# T-11_Version_5.net
KiCad netlist of a schematic drawn in EAGLE
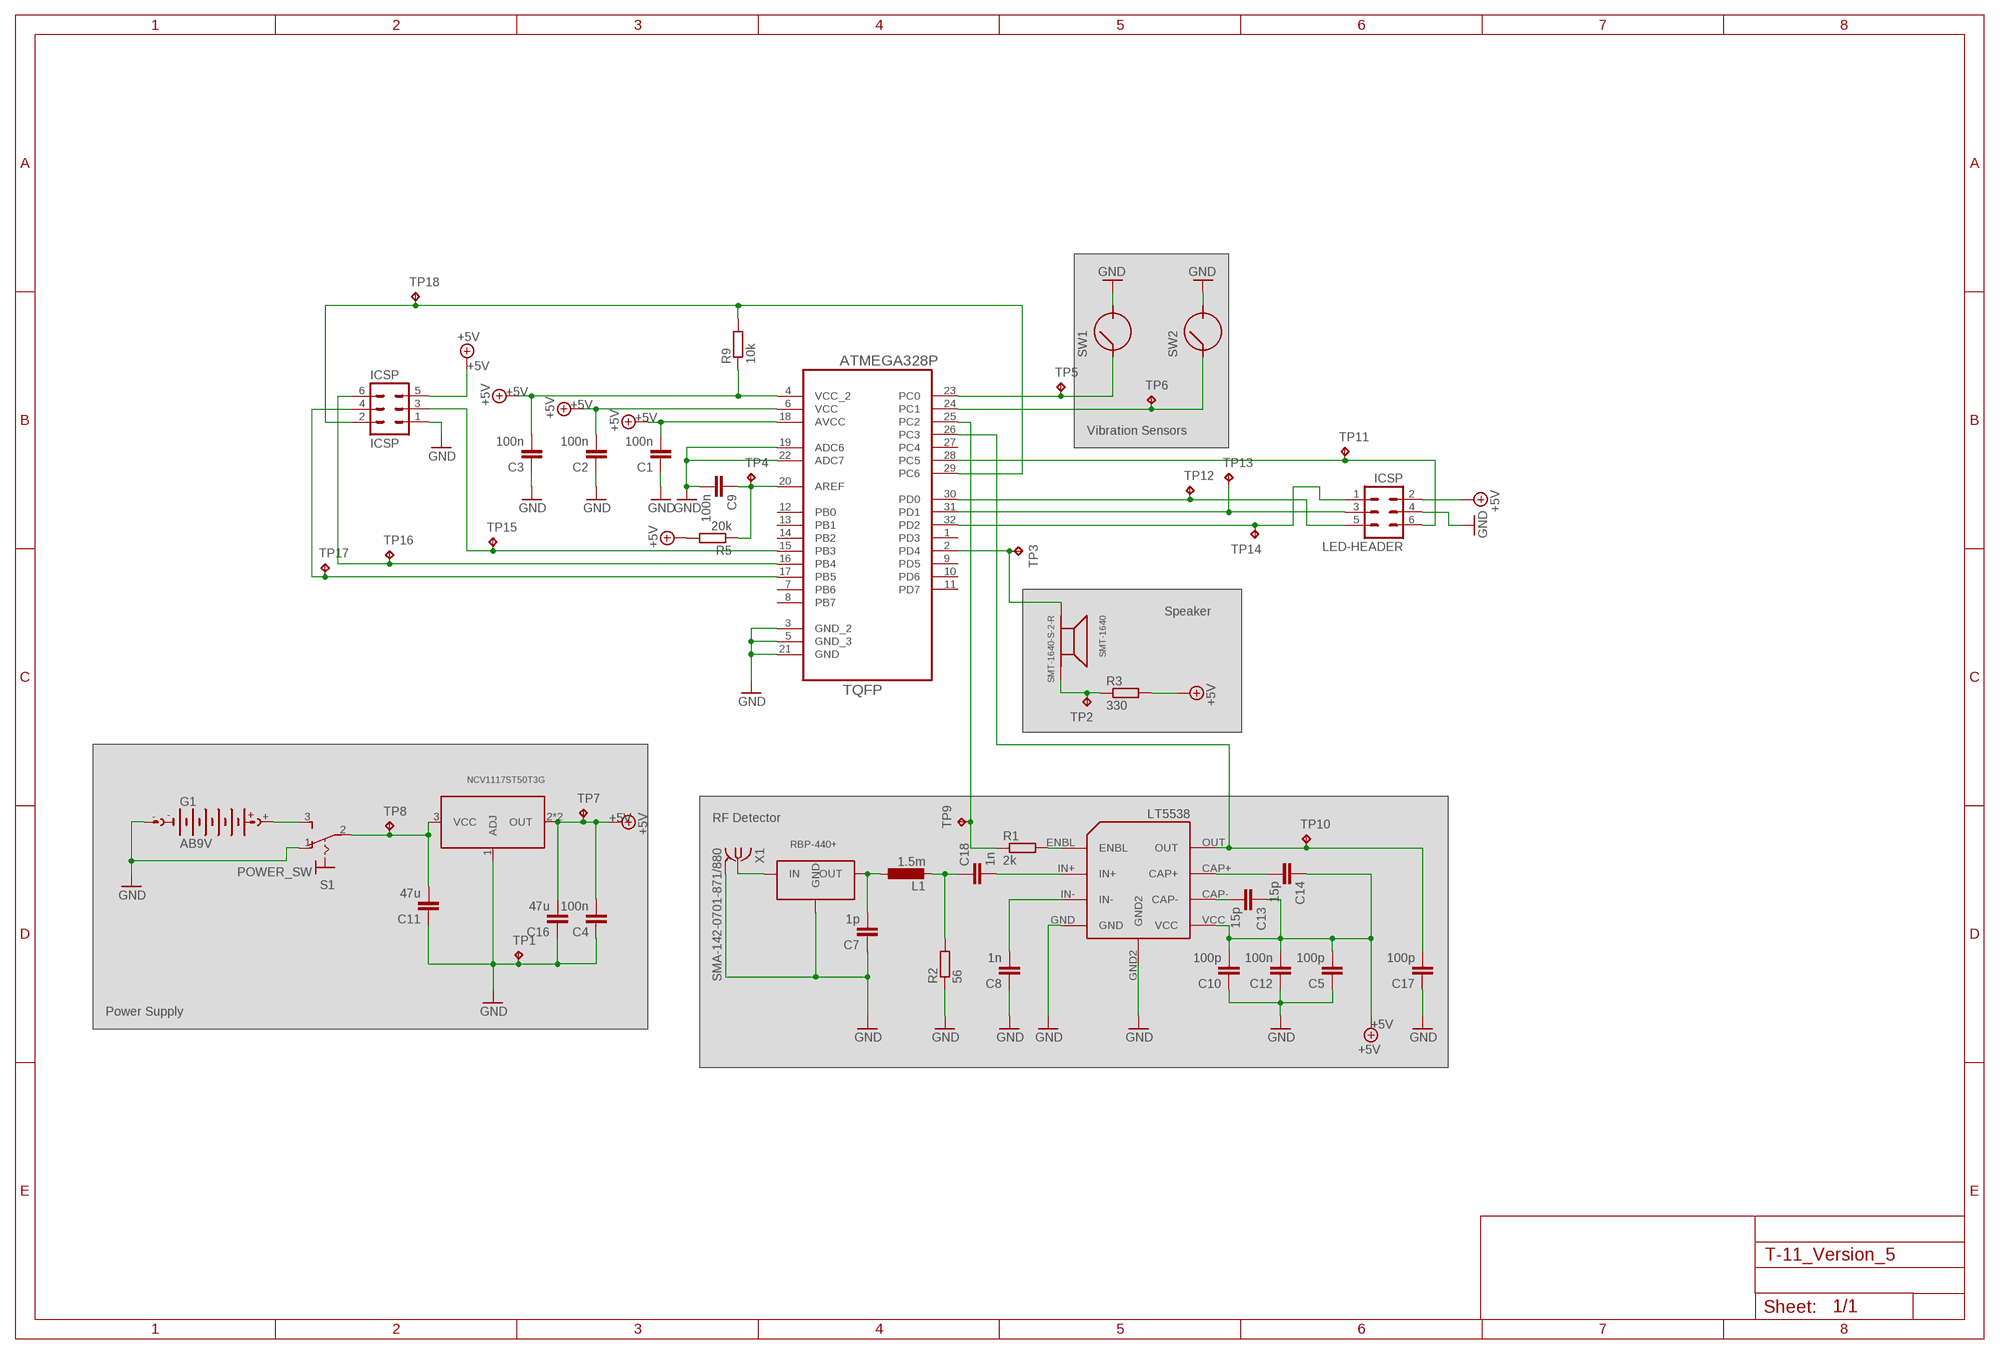
[diagram p0: schematic, sheet 1]

(export (version "E")
  (design (tool "Eeschema 10.0.6"))
  (components
    (comp (ref "C1")
      (value "100n")
      (footprint "eagle-import:C4532")
      (libsource (lib "eagle-import") (part "C-EUC4532"))
    )
    (comp (ref "C2")
      (value "100n")
      (footprint "eagle-import:C4532")
      (libsource (lib "eagle-import") (part "C-EUC4532"))
    )
    (comp (ref "C3")
      (value "100n")
      (footprint "eagle-import:C4532")
      (libsource (lib "eagle-import") (part "C-EUC4532"))
    )
    (comp (ref "C4")
      (value "100n")
      (footprint "eagle-import:C4532")
      (libsource (lib "eagle-import") (part "C-EUC4532"))
    )
    (comp (ref "C5")
      (value "100p")
      (footprint "eagle-import:C4532")
      (libsource (lib "eagle-import") (part "C-EUC4532"))
    )
    (comp (ref "C7")
      (value "1p")
      (footprint "eagle-import:C4532")
      (libsource (lib "eagle-import") (part "C-EUC4532"))
    )
    (comp (ref "C8")
      (value "1n")
      (footprint "eagle-import:C4532")
      (libsource (lib "eagle-import") (part "C-EUC4532"))
    )
    (comp (ref "C9")
      (value "100n")
      (footprint "eagle-import:C4532")
      (libsource (lib "eagle-import") (part "C-EUC4532"))
    )
    (comp (ref "C10")
      (value "100p")
      (footprint "eagle-import:C4532")
      (libsource (lib "eagle-import") (part "C-EUC4532"))
    )
    (comp (ref "C11")
      (value "47u")
      (footprint "eagle-import:C4532")
      (libsource (lib "eagle-import") (part "C-EUC4532"))
    )
    (comp (ref "C12")
      (value "100n")
      (footprint "eagle-import:C4532")
      (libsource (lib "eagle-import") (part "C-EUC4532"))
    )
    (comp (ref "C13")
      (value "15p")
      (footprint "eagle-import:C4532")
      (libsource (lib "eagle-import") (part "C-EUC4532"))
    )
    (comp (ref "C14")
      (value "15p")
      (footprint "eagle-import:C4532")
      (libsource (lib "eagle-import") (part "C-EUC4532"))
    )
    (comp (ref "C16")
      (value "47u")
      (footprint "eagle-import:C4532")
      (libsource (lib "eagle-import") (part "C-EUC4532"))
    )
    (comp (ref "C17")
      (value "100p")
      (footprint "eagle-import:C4532")
      (libsource (lib "eagle-import") (part "C-EUC4532"))
    )
    (comp (ref "C18")
      (value "1n")
      (footprint "eagle-import:C4532")
      (libsource (lib "eagle-import") (part "C-EUC4532"))
    )
    (comp (ref "G1")
      (value "AB9V")
      (footprint "eagle-import:AB9V")
      (libsource (lib "eagle-import") (part "AB9V"))
    )
    (comp (ref "ICSP")
      (value "ICSP")
      (footprint "eagle-import:MA03-2")
      (libsource (lib "eagle-import") (part "MA03-2"))
    )
    (comp (ref "L1")
      (value "1.5m")
      (footprint "eagle-import:L4532P")
      (libsource (lib "eagle-import") (part "L-EUL4532P"))
    )
    (comp (ref "LED-HEADER")
      (value "ICSP")
      (footprint "eagle-import:MA03-2")
      (libsource (lib "eagle-import") (part "MA03-2"))
    )
    (comp (ref "LT5538")
      (value "LT5538")
      (footprint "eagle-import:LT5538")
      (libsource (lib "eagle-import") (part "LT5538"))
    )
    (comp (ref "NVC1")
      (value "NCV1117ST50T3G")
      (footprint "eagle-import:SOT223")
      (libsource (lib "eagle-import") (part "NCV1117ST50T3G"))
    )
    (comp (ref "R1")
      (value "2k")
      (footprint "eagle-import:R3225")
      (libsource (lib "eagle-import") (part "R-EU_R3225"))
    )
    (comp (ref "R2")
      (value "56")
      (footprint "eagle-import:R3225")
      (libsource (lib "eagle-import") (part "R-EU_R3225"))
    )
    (comp (ref "R3")
      (value "330")
      (footprint "eagle-import:R3225")
      (libsource (lib "eagle-import") (part "R-EU_R3225"))
    )
    (comp (ref "R5")
      (value "20k")
      (footprint "eagle-import:R3225")
      (libsource (lib "eagle-import") (part "R-EU_R3225"))
    )
    (comp (ref "R9")
      (value "10k")
      (footprint "eagle-import:R3225")
      (libsource (lib "eagle-import") (part "R-EU_R3225"))
    )
    (comp (ref "RBP-440+")
      (value "RBP-440+")
      (footprint "eagle-import:GP731")
      (libsource (lib "eagle-import") (part "RBP-440+"))
    )
    (comp (ref "S1")
      (value "POWER_SW")
      (footprint "eagle-import:320-916")
      (libsource (lib "eagle-import") (part "320-916"))
    )
    (comp (ref "SMT-1640")
      (value "SMT-1640-S-2-R")
      (footprint "eagle-import:SMT-1640")
      (libsource (lib "eagle-import") (part "SMT-1640-S-2-R"))
    )
    (comp (ref "SW1")
      (value "SW-1801X")
      (footprint "eagle-import:SW-1801X")
      (libsource (lib "eagle-import") (part "SW-1801X"))
    )
    (comp (ref "SW2")
      (value "SW-1801X")
      (footprint "eagle-import:SW-1801X")
      (libsource (lib "eagle-import") (part "SW-1801X"))
    )
    (comp (ref "TP1")
      (value "TPTP10R")
      (footprint "eagle-import:TP10R")
      (libsource (lib "eagle-import") (part "TPTP10R"))
    )
    (comp (ref "TP2")
      (value "TPTP10R")
      (footprint "eagle-import:TP10R")
      (libsource (lib "eagle-import") (part "TPTP10R"))
    )
    (comp (ref "TP3")
      (value "TPTP10R")
      (footprint "eagle-import:TP10R")
      (libsource (lib "eagle-import") (part "TPTP10R"))
    )
    (comp (ref "TP4")
      (value "TPTP10R")
      (footprint "eagle-import:TP10R")
      (libsource (lib "eagle-import") (part "TPTP10R"))
    )
    (comp (ref "TP5")
      (value "TPTP10R")
      (footprint "eagle-import:TP10R")
      (libsource (lib "eagle-import") (part "TPTP10R"))
    )
    (comp (ref "TP6")
      (value "TPTP10R")
      (footprint "eagle-import:TP10R")
      (libsource (lib "eagle-import") (part "TPTP10R"))
    )
    (comp (ref "TP7")
      (value "TPTP10R")
      (footprint "eagle-import:TP10R")
      (libsource (lib "eagle-import") (part "TPTP10R"))
    )
    (comp (ref "TP8")
      (value "TPTP10R")
      (footprint "eagle-import:TP10R")
      (libsource (lib "eagle-import") (part "TPTP10R"))
    )
    (comp (ref "TP9")
      (value "TPTP10R")
      (footprint "eagle-import:TP10R")
      (libsource (lib "eagle-import") (part "TPTP10R"))
    )
    (comp (ref "TP10")
      (value "TPTP10R")
      (footprint "eagle-import:TP10R")
      (libsource (lib "eagle-import") (part "TPTP10R"))
    )
    (comp (ref "TP11")
      (value "TPTP10R")
      (footprint "eagle-import:TP10R")
      (libsource (lib "eagle-import") (part "TPTP10R"))
    )
    (comp (ref "TP12")
      (value "TPTP10R")
      (footprint "eagle-import:TP10R")
      (libsource (lib "eagle-import") (part "TPTP10R"))
    )
    (comp (ref "TP13")
      (value "TPTP10R")
      (footprint "eagle-import:TP10R")
      (libsource (lib "eagle-import") (part "TPTP10R"))
    )
    (comp (ref "TP14")
      (value "TPTP10R")
      (footprint "eagle-import:TP10R")
      (libsource (lib "eagle-import") (part "TPTP10R"))
    )
    (comp (ref "TP15")
      (value "TPTP10R")
      (footprint "eagle-import:TP10R")
      (libsource (lib "eagle-import") (part "TPTP10R"))
    )
    (comp (ref "TP16")
      (value "TPTP10R")
      (footprint "eagle-import:TP10R")
      (libsource (lib "eagle-import") (part "TPTP10R"))
    )
    (comp (ref "TP17")
      (value "TPTP10R")
      (footprint "eagle-import:TP10R")
      (libsource (lib "eagle-import") (part "TPTP10R"))
    )
    (comp (ref "TP18")
      (value "TPTP10R")
      (footprint "eagle-import:TP10R")
      (libsource (lib "eagle-import") (part "TPTP10R"))
    )
    (comp (ref "U1")
      (value "ATMEGA328P-AU")
      (footprint "eagle-import:QFP80P900X900X120-32N")
      (libsource (lib "eagle-import") (part "ATMEGA328P-AU"))
    )
    (comp (ref "X1")
      (value "SMA-142-0701-871/880")
      (footprint "eagle-import:SMA-142-0701-871")
      (fields (field (name "MF") "JOHNSON COMPONENTS") (field (name "MPN") "142-0701-871"))
      (libsource (lib "eagle-import") (part "SMA-142-0701-871/880"))
    )
  )
  (nets
    (net (code "1") (name "+5V") (class "Default")
      (node (ref "C1") (pin "2") (pinfunction "2_2") (pintype "passive"))
      (node (ref "C10") (pin "2") (pinfunction "2_2") (pintype "passive"))
      (node (ref "C12") (pin "2") (pinfunction "2_2") (pintype "passive"))
      (node (ref "C13") (pin "1") (pinfunction "1_1") (pintype "passive"))
      (node (ref "C14") (pin "1") (pinfunction "1_1") (pintype "passive"))
      (node (ref "C16") (pin "2") (pinfunction "2_2") (pintype "passive"))
      (node (ref "C2") (pin "2") (pinfunction "2_2") (pintype "passive"))
      (node (ref "C3") (pin "2") (pinfunction "2_2") (pintype "passive"))
      (node (ref "C4") (pin "2") (pinfunction "2_2") (pintype "passive"))
      (node (ref "C5") (pin "2") (pinfunction "2_2") (pintype "passive"))
      (node (ref "ICSP") (pin "5") (pinfunction "5_5") (pintype "passive"))
      (node (ref "LED-HEADER") (pin "2") (pinfunction "2_2") (pintype "passive"))
      (node (ref "LT5538") (pin "VCC") (pinfunction "VCC_VCC") (pintype "power_in"))
      (node (ref "NVC1") (pin "2") (pinfunction "OUT_2") (pintype "power_in"))
      (node (ref "NVC1") (pin "4") (pinfunction "OUT_4") (pintype "power_in"))
      (node (ref "R3") (pin "2") (pinfunction "2_2") (pintype "passive"))
      (node (ref "R5") (pin "2") (pinfunction "2_2") (pintype "passive"))
      (node (ref "R9") (pin "1") (pinfunction "1_1") (pintype "passive"))
      (node (ref "TP7") (pin "TP") (pinfunction "TP_TP") (pintype "input"))
      (node (ref "U1") (pin "18") (pinfunction "AVCC_18") (pintype "power_in"))
      (node (ref "U1") (pin "4") (pinfunction "VCC_2_4") (pintype "power_in"))
      (node (ref "U1") (pin "6") (pinfunction "VCC_6") (pintype "power_in"))
    )
    (net (code "2") (name "GND") (class "Default")
      (node (ref "C1") (pin "1") (pinfunction "1_1") (pintype "passive"))
      (node (ref "C10") (pin "1") (pinfunction "1_1") (pintype "passive"))
      (node (ref "C11") (pin "1") (pinfunction "1_1") (pintype "passive"))
      (node (ref "C12") (pin "1") (pinfunction "1_1") (pintype "passive"))
      (node (ref "C16") (pin "1") (pinfunction "1_1") (pintype "passive"))
      (node (ref "C17") (pin "1") (pinfunction "1_1") (pintype "passive"))
      (node (ref "C2") (pin "1") (pinfunction "1_1") (pintype "passive"))
      (node (ref "C3") (pin "1") (pinfunction "1_1") (pintype "passive"))
      (node (ref "C4") (pin "1") (pinfunction "1_1") (pintype "passive"))
      (node (ref "C5") (pin "1") (pinfunction "1_1") (pintype "passive"))
      (node (ref "C7") (pin "1") (pinfunction "1_1") (pintype "passive"))
      (node (ref "C8") (pin "1") (pinfunction "1_1") (pintype "passive"))
      (node (ref "C9") (pin "2") (pinfunction "2_2") (pintype "passive"))
      (node (ref "G1") (pin "-") (pinfunction "-_-") (pintype "passive"))
      (node (ref "ICSP") (pin "1") (pinfunction "1_1") (pintype "passive"))
      (node (ref "LED-HEADER") (pin "4") (pinfunction "4_4") (pintype "passive"))
      (node (ref "LT5538") (pin "GND") (pinfunction "GND_GND") (pintype "power_in"))
      (node (ref "LT5538") (pin "GND2") (pinfunction "GND2_GND2") (pintype "bidirectional"))
      (node (ref "NVC1") (pin "1") (pinfunction "ADJ_1") (pintype "bidirectional"))
      (node (ref "R2") (pin "1") (pinfunction "1_1") (pintype "passive"))
      (node (ref "RBP-440+") (pin "1") (pinfunction "GND_1") (pintype "power_in"))
      (node (ref "RBP-440+") (pin "3") (pinfunction "GND_3") (pintype "power_in"))
      (node (ref "RBP-440+") (pin "4") (pinfunction "GND_4") (pintype "power_in"))
      (node (ref "RBP-440+") (pin "5") (pinfunction "GND_5") (pintype "power_in"))
      (node (ref "RBP-440+") (pin "7") (pinfunction "GND_7") (pintype "power_in"))
      (node (ref "RBP-440+") (pin "8") (pinfunction "GND_8") (pintype "power_in"))
      (node (ref "S1") (pin "1") (pinfunction "O_1") (pintype "passive"))
      (node (ref "SW1") (pin "P$2") (pinfunction "P$2_P$2") (pintype "bidirectional"))
      (node (ref "SW2") (pin "P$2") (pinfunction "P$2_P$2") (pintype "bidirectional"))
      (node (ref "TP1") (pin "TP") (pinfunction "TP_TP") (pintype "input"))
      (node (ref "U1") (pin "19") (pinfunction "ADC6_19") (pintype "input"))
      (node (ref "U1") (pin "21") (pinfunction "GND_21") (pintype "passive"))
      (node (ref "U1") (pin "22") (pinfunction "ADC7_22") (pintype "input"))
      (node (ref "U1") (pin "3") (pinfunction "GND_2_3") (pintype "passive"))
      (node (ref "U1") (pin "5") (pinfunction "GND_3_5") (pintype "passive"))
      (node (ref "X1") (pin "2@1") (pinfunction "2_2@1") (pintype "passive"))
      (node (ref "X1") (pin "2@2") (pinfunction "2_2@2") (pintype "passive"))
      (node (ref "X1") (pin "2@3") (pinfunction "2_2@3") (pintype "passive"))
      (node (ref "X1") (pin "2@4") (pinfunction "2_2@4") (pintype "passive"))
    )
    (net (code "3") (name "Net-(C8-Pad2)") (class "Default")
      (node (ref "C8") (pin "2") (pinfunction "2_2") (pintype "passive"))
      (node (ref "LT5538") (pin "IN-") (pinfunction "IN-_IN-") (pintype "bidirectional"))
    )
    (net (code "4") (name "Net-(C13-Pad2)") (class "Default")
      (node (ref "C13") (pin "2") (pinfunction "2_2") (pintype "passive"))
      (node (ref "LT5538") (pin "CAP-") (pinfunction "CAP-_CAP-") (pintype "bidirectional"))
    )
    (net (code "5") (name "Net-(C14-Pad2)") (class "Default")
      (node (ref "C14") (pin "2") (pinfunction "2_2") (pintype "passive"))
      (node (ref "LT5538") (pin "CAP+") (pinfunction "CAP+_CAP+") (pintype "bidirectional"))
    )
    (net (code "6") (name "Net-(C18-Pad1)") (class "Default")
      (node (ref "C18") (pin "1") (pinfunction "1_1") (pintype "passive"))
      (node (ref "L1") (pin "2") (pinfunction "2_2") (pintype "passive"))
      (node (ref "R2") (pin "2") (pinfunction "2_2") (pintype "passive"))
    )
    (net (code "7") (name "Net-(C18-Pad2)") (class "Default")
      (node (ref "C18") (pin "2") (pinfunction "2_2") (pintype "passive"))
      (node (ref "LT5538") (pin "IN+") (pinfunction "IN+_IN+") (pintype "bidirectional"))
    )
    (net (code "8") (name "Net-(LT5538-PadENBL)") (class "Default")
      (node (ref "LT5538") (pin "ENBL") (pinfunction "ENBL_ENBL") (pintype "bidirectional"))
      (node (ref "R1") (pin "2") (pinfunction "2_2") (pintype "passive"))
    )
    (net (code "9") (name "Net-(NVC1-VCC)") (class "Default")
      (node (ref "C11") (pin "2") (pinfunction "2_2") (pintype "passive"))
      (node (ref "NVC1") (pin "3") (pinfunction "VCC_3") (pintype "input"))
      (node (ref "S1") (pin "2") (pinfunction "P_2") (pintype "passive"))
      (node (ref "TP8") (pin "TP") (pinfunction "TP_TP") (pintype "input"))
    )
    (net (code "10") (name "Net-(RBP-440+-IN)") (class "Default")
      (node (ref "RBP-440+") (pin "2") (pinfunction "IN_2") (pintype "bidirectional"))
      (node (ref "X1") (pin "1") (pinfunction "1_1") (pintype "passive"))
    )
    (net (code "11") (name "Net-(RBP-440+-OUT)") (class "Default")
      (node (ref "C7") (pin "2") (pinfunction "2_2") (pintype "passive"))
      (node (ref "L1") (pin "1") (pinfunction "1_1") (pintype "passive"))
      (node (ref "RBP-440+") (pin "6") (pinfunction "OUT_6") (pintype "output"))
    )
    (net (code "12") (name "Net-(S1-S)") (class "Default")
      (node (ref "G1") (pin "+") (pinfunction "+_+") (pintype "passive"))
      (node (ref "S1") (pin "3") (pinfunction "S_3") (pintype "passive"))
    )
    (net (code "13") (name "Net-(SMT-1640-IN)") (class "Default")
      (node (ref "SMT-1640") (pin "P$2") (pinfunction "IN_P$2") (pintype "bidirectional"))
      (node (ref "TP3") (pin "TP") (pinfunction "TP_TP") (pintype "input"))
      (node (ref "U1") (pin "2") (pinfunction "PD4_2") (pintype "bidirectional"))
    )
    (net (code "14") (name "Net-(SMT-1640-OUT)") (class "Default")
      (node (ref "R3") (pin "1") (pinfunction "1_1") (pintype "passive"))
      (node (ref "SMT-1640") (pin "P$1") (pinfunction "OUT_P$1") (pintype "bidirectional"))
      (node (ref "TP2") (pin "TP") (pinfunction "TP_TP") (pintype "input"))
    )
    (net (code "15") (name "Net-(U1-AREF)") (class "Default")
      (node (ref "C9") (pin "1") (pinfunction "1_1") (pintype "passive"))
      (node (ref "R5") (pin "1") (pinfunction "1_1") (pintype "passive"))
      (node (ref "TP4") (pin "TP") (pinfunction "TP_TP") (pintype "input"))
      (node (ref "U1") (pin "20") (pinfunction "AREF_20") (pintype "input"))
    )
    (net (code "16") (name "Net-(U1-PB3)") (class "Default")
      (node (ref "ICSP") (pin "3") (pinfunction "3_3") (pintype "passive"))
      (node (ref "TP15") (pin "TP") (pinfunction "TP_TP") (pintype "input"))
      (node (ref "U1") (pin "15") (pinfunction "PB3_15") (pintype "bidirectional"))
    )
    (net (code "17") (name "Net-(U1-PB4)") (class "Default")
      (node (ref "ICSP") (pin "6") (pinfunction "6_6") (pintype "passive"))
      (node (ref "TP16") (pin "TP") (pinfunction "TP_TP") (pintype "input"))
      (node (ref "U1") (pin "16") (pinfunction "PB4_16") (pintype "bidirectional"))
    )
    (net (code "18") (name "Net-(U1-PB5)") (class "Default")
      (node (ref "ICSP") (pin "4") (pinfunction "4_4") (pintype "passive"))
      (node (ref "TP17") (pin "TP") (pinfunction "TP_TP") (pintype "input"))
      (node (ref "U1") (pin "17") (pinfunction "PB5_17") (pintype "bidirectional"))
    )
    (net (code "19") (name "Net-(U1-PC0)") (class "Default")
      (node (ref "SW1") (pin "P$1") (pinfunction "P$1_P$1") (pintype "bidirectional"))
      (node (ref "TP5") (pin "TP") (pinfunction "TP_TP") (pintype "input"))
      (node (ref "U1") (pin "23") (pinfunction "PC0_23") (pintype "bidirectional"))
    )
    (net (code "20") (name "Net-(U1-PC1)") (class "Default")
      (node (ref "SW2") (pin "P$1") (pinfunction "P$1_P$1") (pintype "bidirectional"))
      (node (ref "TP6") (pin "TP") (pinfunction "TP_TP") (pintype "input"))
      (node (ref "U1") (pin "24") (pinfunction "PC1_24") (pintype "bidirectional"))
    )
    (net (code "21") (name "Net-(U1-PC2)") (class "Default")
      (node (ref "R1") (pin "1") (pinfunction "1_1") (pintype "passive"))
      (node (ref "TP9") (pin "TP") (pinfunction "TP_TP") (pintype "input"))
      (node (ref "U1") (pin "25") (pinfunction "PC2_25") (pintype "bidirectional"))
    )
    (net (code "22") (name "Net-(U1-PC3)") (class "Default")
      (node (ref "C17") (pin "2") (pinfunction "2_2") (pintype "passive"))
      (node (ref "LT5538") (pin "OUT") (pinfunction "OUT_OUT") (pintype "output"))
      (node (ref "TP10") (pin "TP") (pinfunction "TP_TP") (pintype "input"))
      (node (ref "U1") (pin "26") (pinfunction "PC3_26") (pintype "bidirectional"))
    )
    (net (code "23") (name "Net-(U1-PC5)") (class "Default")
      (node (ref "LED-HEADER") (pin "6") (pinfunction "6_6") (pintype "passive"))
      (node (ref "TP11") (pin "TP") (pinfunction "TP_TP") (pintype "input"))
      (node (ref "U1") (pin "28") (pinfunction "PC5_28") (pintype "bidirectional"))
    )
    (net (code "24") (name "Net-(U1-PC6)") (class "Default")
      (node (ref "ICSP") (pin "2") (pinfunction "2_2") (pintype "passive"))
      (node (ref "R9") (pin "2") (pinfunction "2_2") (pintype "passive"))
      (node (ref "TP18") (pin "TP") (pinfunction "TP_TP") (pintype "input"))
      (node (ref "U1") (pin "29") (pinfunction "PC6_29") (pintype "bidirectional"))
    )
    (net (code "25") (name "Net-(U1-PD0)") (class "Default")
      (node (ref "LED-HEADER") (pin "5") (pinfunction "5_5") (pintype "passive"))
      (node (ref "TP12") (pin "TP") (pinfunction "TP_TP") (pintype "input"))
      (node (ref "U1") (pin "30") (pinfunction "PD0_30") (pintype "bidirectional"))
    )
    (net (code "26") (name "Net-(U1-PD1)") (class "Default")
      (node (ref "LED-HEADER") (pin "3") (pinfunction "3_3") (pintype "passive"))
      (node (ref "TP13") (pin "TP") (pinfunction "TP_TP") (pintype "input"))
      (node (ref "U1") (pin "31") (pinfunction "PD1_31") (pintype "bidirectional"))
    )
    (net (code "27") (name "Net-(U1-PD2)") (class "Default")
      (node (ref "LED-HEADER") (pin "1") (pinfunction "1_1") (pintype "passive"))
      (node (ref "TP14") (pin "TP") (pinfunction "TP_TP") (pintype "input"))
      (node (ref "U1") (pin "32") (pinfunction "PD2_32") (pintype "bidirectional"))
    )
    (net (code "28") (name "unconnected-(U1-PB0-Pad12)") (class "Default")
      (node (ref "U1") (pin "12") (pinfunction "PB0_12") (pintype "bidirectional"))
    )
    (net (code "29") (name "unconnected-(U1-PB1-Pad13)") (class "Default")
      (node (ref "U1") (pin "13") (pinfunction "PB1_13") (pintype "bidirectional"))
    )
    (net (code "30") (name "unconnected-(U1-PB2-Pad14)") (class "Default")
      (node (ref "U1") (pin "14") (pinfunction "PB2_14") (pintype "bidirectional"))
    )
    (net (code "31") (name "unconnected-(U1-PB6-Pad7)") (class "Default")
      (node (ref "U1") (pin "7") (pinfunction "PB6_7") (pintype "bidirectional"))
    )
    (net (code "32") (name "unconnected-(U1-PB7-Pad8)") (class "Default")
      (node (ref "U1") (pin "8") (pinfunction "PB7_8") (pintype "bidirectional"))
    )
    (net (code "33") (name "unconnected-(U1-PC4-Pad27)") (class "Default")
      (node (ref "U1") (pin "27") (pinfunction "PC4_27") (pintype "bidirectional"))
    )
    (net (code "34") (name "unconnected-(U1-PD3-Pad1)") (class "Default")
      (node (ref "U1") (pin "1") (pinfunction "PD3_1") (pintype "bidirectional"))
    )
    (net (code "35") (name "unconnected-(U1-PD5-Pad9)") (class "Default")
      (node (ref "U1") (pin "9") (pinfunction "PD5_9") (pintype "bidirectional"))
    )
    (net (code "36") (name "unconnected-(U1-PD6-Pad10)") (class "Default")
      (node (ref "U1") (pin "10") (pinfunction "PD6_10") (pintype "bidirectional"))
    )
    (net (code "37") (name "unconnected-(U1-PD7-Pad11)") (class "Default")
      (node (ref "U1") (pin "11") (pinfunction "PD7_11") (pintype "bidirectional"))
    )
  )
)
